# Ambilight-discovery_bachp_V1_2.net
KiCad netlist of a schematic drawn in EAGLE
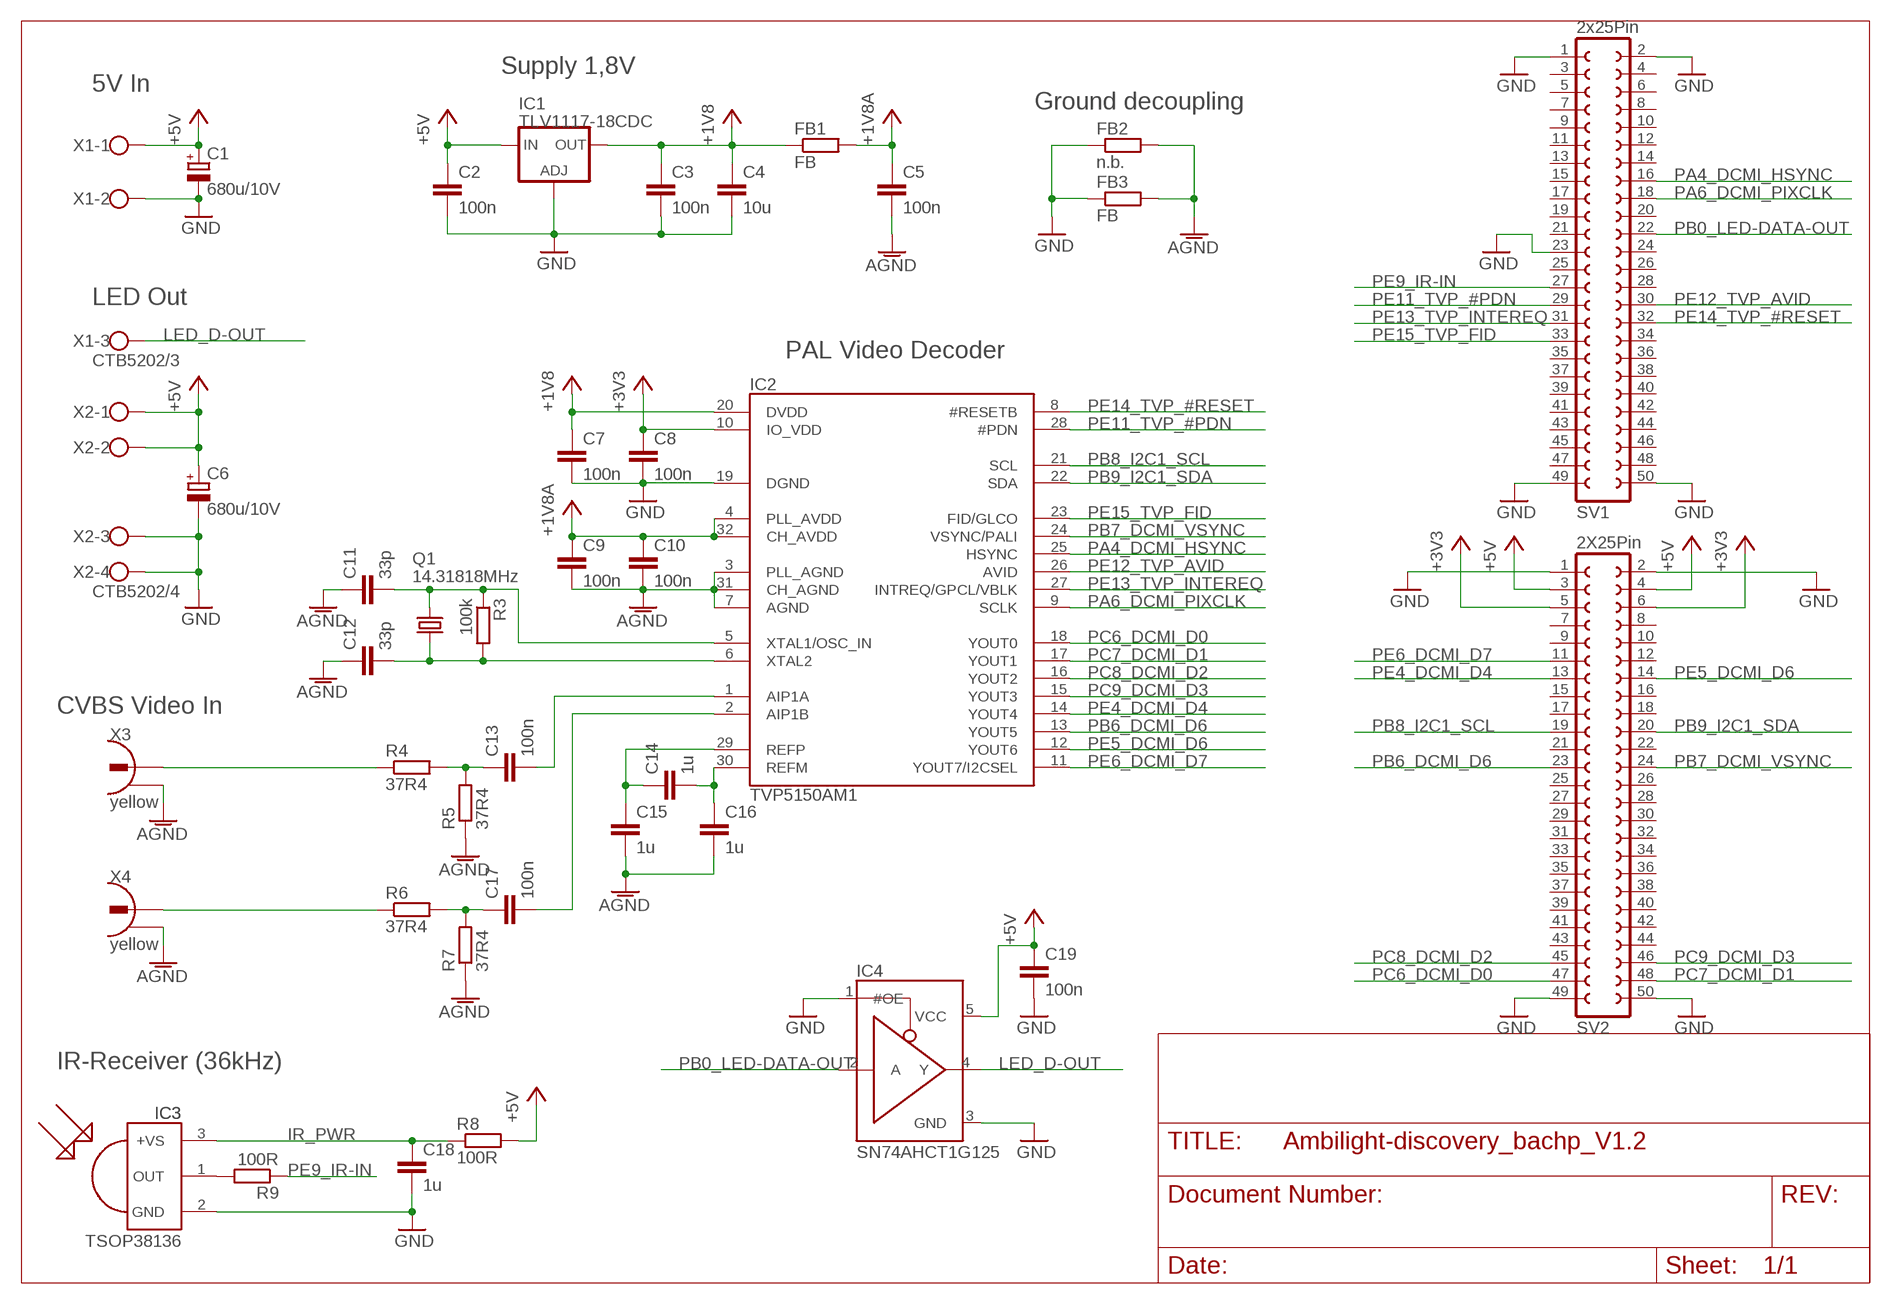
[diagram p0: schematic, sheet 1]

(export (version "E")
  (design (tool "Eeschema 10.0.6"))
  (components
    (comp (ref "C1")
      (value "680u/10V")
      (footprint "eagle-import:153CLV-1012")
      (libsource (lib "eagle-import") (part "CPOL-EU153CLV-1012"))
    )
    (comp (ref "C2")
      (value "100n")
      (footprint "eagle-import:C0805")
      (libsource (lib "eagle-import") (part "C-EUC0805"))
    )
    (comp (ref "C3")
      (value "100n")
      (footprint "eagle-import:C0805")
      (libsource (lib "eagle-import") (part "C-EUC0805"))
    )
    (comp (ref "C4")
      (value "10u")
      (footprint "eagle-import:C1210")
      (libsource (lib "eagle-import") (part "C-EUC1210"))
    )
    (comp (ref "C5")
      (value "100n")
      (footprint "eagle-import:C0805")
      (libsource (lib "eagle-import") (part "C-EUC0805"))
    )
    (comp (ref "C6")
      (value "680u/10V")
      (footprint "eagle-import:153CLV-1012")
      (libsource (lib "eagle-import") (part "CPOL-EU153CLV-1012"))
    )
    (comp (ref "C7")
      (value "100n")
      (footprint "eagle-import:C0805")
      (libsource (lib "eagle-import") (part "C-EUC0805"))
    )
    (comp (ref "C8")
      (value "100n")
      (footprint "eagle-import:C0805")
      (libsource (lib "eagle-import") (part "C-EUC0805"))
    )
    (comp (ref "C9")
      (value "100n")
      (footprint "eagle-import:C0805")
      (libsource (lib "eagle-import") (part "C-EUC0805"))
    )
    (comp (ref "C10")
      (value "100n")
      (footprint "eagle-import:C0805")
      (libsource (lib "eagle-import") (part "C-EUC0805"))
    )
    (comp (ref "C11")
      (value "33p")
      (footprint "eagle-import:C0805")
      (libsource (lib "eagle-import") (part "C-EUC0805"))
    )
    (comp (ref "C12")
      (value "33p")
      (footprint "eagle-import:C0805")
      (libsource (lib "eagle-import") (part "C-EUC0805"))
    )
    (comp (ref "C13")
      (value "100n")
      (footprint "eagle-import:C0805")
      (libsource (lib "eagle-import") (part "C-EUC0805"))
    )
    (comp (ref "C14")
      (value "1u")
      (footprint "eagle-import:C0805")
      (libsource (lib "eagle-import") (part "C-EUC0805"))
    )
    (comp (ref "C15")
      (value "1u")
      (footprint "eagle-import:C0805")
      (libsource (lib "eagle-import") (part "C-EUC0805"))
    )
    (comp (ref "C16")
      (value "1u")
      (footprint "eagle-import:C0805")
      (libsource (lib "eagle-import") (part "C-EUC0805"))
    )
    (comp (ref "C17")
      (value "100n")
      (footprint "eagle-import:C0805")
      (libsource (lib "eagle-import") (part "C-EUC0805"))
    )
    (comp (ref "C18")
      (value "1u")
      (footprint "eagle-import:C0805")
      (libsource (lib "eagle-import") (part "C-EUC0805"))
    )
    (comp (ref "C19")
      (value "100n")
      (footprint "eagle-import:C0805")
      (libsource (lib "eagle-import") (part "C-EUC0805"))
    )
    (comp (ref "FB1")
      (value "FB")
      (footprint "eagle-import:R0805")
      (libsource (lib "eagle-import") (part "R-EU_R0805"))
    )
    (comp (ref "FB2")
      (value "n.b.")
      (footprint "eagle-import:R0805")
      (libsource (lib "eagle-import") (part "R-EU_R0805"))
    )
    (comp (ref "FB3")
      (value "FB")
      (footprint "eagle-import:R0805")
      (libsource (lib "eagle-import") (part "R-EU_R0805"))
    )
    (comp (ref "IC1")
      (value "TLV1117-18CDC")
      (footprint "eagle-import:SOT223")
      (libsource (lib "eagle-import") (part "LD117A?S18TR"))
    )
    (comp (ref "IC2")
      (value "TVP5150AM1")
      (footprint "eagle-import:TQFP32-0.5MM")
      (libsource (lib "eagle-import") (part "TVP5150AM1"))
    )
    (comp (ref "IC3")
      (value "TSOP38136")
      (footprint "eagle-import:TSOP38XXX")
      (libsource (lib "eagle-import") (part "TSOP38136"))
    )
    (comp (ref "IC4")
      (value "SN74AHCT1G125")
      (footprint "eagle-import:SOT23-5L")
      (libsource (lib "eagle-import") (part "SN74AHCT1G125"))
    )
    (comp (ref "Q1")
      (value "14.31818MHz")
      (footprint "eagle-import:HC49UP")
      (libsource (lib "eagle-import") (part "CRYSTALHC49UP"))
    )
    (comp (ref "R3")
      (value "100k")
      (footprint "eagle-import:R0805")
      (libsource (lib "eagle-import") (part "R-EU_R0805"))
    )
    (comp (ref "R4")
      (value "37R4")
      (footprint "eagle-import:R0805")
      (libsource (lib "eagle-import") (part "R-EU_R0805"))
    )
    (comp (ref "R5")
      (value "37R4")
      (footprint "eagle-import:R0805")
      (libsource (lib "eagle-import") (part "R-EU_R0805"))
    )
    (comp (ref "R6")
      (value "37R4")
      (footprint "eagle-import:R0805")
      (libsource (lib "eagle-import") (part "R-EU_R0805"))
    )
    (comp (ref "R7")
      (value "37R4")
      (footprint "eagle-import:R0805")
      (libsource (lib "eagle-import") (part "R-EU_R0805"))
    )
    (comp (ref "R8")
      (value "100R")
      (footprint "eagle-import:R0805")
      (libsource (lib "eagle-import") (part "R-EU_R0805"))
    )
    (comp (ref "R9")
      (value "100R")
      (footprint "eagle-import:R0805")
      (libsource (lib "eagle-import") (part "R-EU_R0805"))
    )
    (comp (ref "SV1")
      (value "2x25Pin")
      (footprint "eagle-import:FE25-2")
      (libsource (lib "eagle-import") (part "FE25-2"))
    )
    (comp (ref "SV2")
      (value "2X25Pin")
      (footprint "eagle-import:FE25-2")
      (libsource (lib "eagle-import") (part "FE25-2"))
    )
    (comp (ref "X1")
      (value "CTB5202/3")
      (footprint "eagle-import:W237-103")
      (fields (field (name "MPN") "237-103"))
      (libsource (lib "eagle-import") (part "W237-103"))
    )
    (comp (ref "X2")
      (value "CTB5202/4")
      (footprint "eagle-import:W237-4")
      (libsource (lib "eagle-import") (part "W237-4"))
    )
    (comp (ref "X3")
      (value "yellow")
      (footprint "eagle-import:CINCH_JALCO")
      (libsource (lib "eagle-import") (part "CINCH_JALCO"))
    )
    (comp (ref "X4")
      (value "yellow")
      (footprint "eagle-import:CINCH_JALCO")
      (libsource (lib "eagle-import") (part "CINCH_JALCO"))
    )
  )
  (nets
    (net (code "1") (name "+1V8") (class "Default")
      (node (ref "C3") (pin "1") (pinfunction "1_1") (pintype "passive"))
      (node (ref "C4") (pin "1") (pinfunction "1_1") (pintype "passive"))
      (node (ref "C7") (pin "1") (pinfunction "1_1") (pintype "passive"))
      (node (ref "FB1") (pin "1") (pinfunction "1_1") (pintype "passive"))
      (node (ref "IC1") (pin "2") (pinfunction "OUT_2") (pintype "passive"))
      (node (ref "IC1") (pin "4") (pinfunction "OUT_4") (pintype "passive"))
      (node (ref "IC2") (pin "20") (pinfunction "DVDD_20") (pintype "power_in"))
    )
    (net (code "2") (name "+1V8A") (class "Default")
      (node (ref "C10") (pin "1") (pinfunction "1_1") (pintype "passive"))
      (node (ref "C5") (pin "1") (pinfunction "1_1") (pintype "passive"))
      (node (ref "C9") (pin "1") (pinfunction "1_1") (pintype "passive"))
      (node (ref "FB1") (pin "2") (pinfunction "2_2") (pintype "passive"))
      (node (ref "IC2") (pin "32") (pinfunction "CH_AVDD_32") (pintype "power_in"))
      (node (ref "IC2") (pin "4") (pinfunction "PLL_AVDD_4") (pintype "power_in"))
    )
    (net (code "3") (name "+3V3") (class "Default")
      (node (ref "C8") (pin "1") (pinfunction "1_1") (pintype "passive"))
      (node (ref "IC2") (pin "10") (pinfunction "IO_VDD_10") (pintype "power_in"))
      (node (ref "SV2") (pin "5") (pinfunction "5_5") (pintype "passive"))
      (node (ref "SV2") (pin "6") (pinfunction "6_6") (pintype "passive"))
    )
    (net (code "4") (name "+5V") (class "Default")
      (node (ref "C1") (pin "+") (pinfunction "+_+") (pintype "passive"))
      (node (ref "C19") (pin "1") (pinfunction "1_1") (pintype "passive"))
      (node (ref "C2") (pin "1") (pinfunction "1_1") (pintype "passive"))
      (node (ref "C6") (pin "+") (pinfunction "+_+") (pintype "passive"))
      (node (ref "IC1") (pin "3") (pinfunction "IN_3") (pintype "input"))
      (node (ref "IC4") (pin "5") (pinfunction "VCC_5") (pintype "power_in"))
      (node (ref "R8") (pin "2") (pinfunction "2_2") (pintype "passive"))
      (node (ref "SV2") (pin "3") (pinfunction "3_3") (pintype "passive"))
      (node (ref "SV2") (pin "4") (pinfunction "4_4") (pintype "passive"))
      (node (ref "X1") (pin "1") (pinfunction "KL_1") (pintype "passive"))
      (node (ref "X2") (pin "1") (pinfunction "KL_1") (pintype "passive"))
      (node (ref "X2") (pin "2") (pinfunction "KL_2") (pintype "passive"))
    )
    (net (code "5") (name "/IR_PWR") (class "Default")
      (node (ref "C18") (pin "1") (pinfunction "1_1") (pintype "passive"))
      (node (ref "IC3") (pin "3") (pinfunction "+VS_3") (pintype "power_in"))
      (node (ref "R8") (pin "1") (pinfunction "1_1") (pintype "passive"))
    )
    (net (code "6") (name "/LED_D-OUT") (class "Default")
      (node (ref "IC4") (pin "4") (pinfunction "Y_4") (pintype "output"))
      (node (ref "X1") (pin "3") (pinfunction "KL_3") (pintype "passive"))
    )
    (net (code "7") (name "/PA4_DCMI_HSYNC") (class "Default")
      (node (ref "IC2") (pin "25") (pinfunction "HSYNC_25") (pintype "output"))
      (node (ref "SV1") (pin "16") (pinfunction "16_16") (pintype "passive"))
    )
    (net (code "8") (name "/PA6_DCMI_PIXCLK") (class "Default")
      (node (ref "IC2") (pin "9") (pinfunction "SCLK_9") (pintype "output"))
      (node (ref "SV1") (pin "18") (pinfunction "18_18") (pintype "passive"))
    )
    (net (code "9") (name "/PB0_LED-DATA-OUT") (class "Default")
      (node (ref "IC4") (pin "2") (pinfunction "A_2") (pintype "input"))
      (node (ref "SV1") (pin "22") (pinfunction "22_22") (pintype "passive"))
    )
    (net (code "10") (name "/PB6_DCMI_D6") (class "Default")
      (node (ref "IC2") (pin "13") (pinfunction "YOUT5_13") (pintype "output"))
      (node (ref "SV2") (pin "23") (pinfunction "23_23") (pintype "passive"))
    )
    (net (code "11") (name "/PB7_DCMI_VSYNC") (class "Default")
      (node (ref "IC2") (pin "24") (pinfunction "VSYNC/PALI_24") (pintype "output"))
      (node (ref "SV2") (pin "24") (pinfunction "24_24") (pintype "passive"))
    )
    (net (code "12") (name "/PB8_I2C1_SCL") (class "Default")
      (node (ref "IC2") (pin "21") (pinfunction "SCL_21") (pintype "bidirectional"))
      (node (ref "SV2") (pin "19") (pinfunction "19_19") (pintype "passive"))
    )
    (net (code "13") (name "/PB9_I2C1_SDA") (class "Default")
      (node (ref "IC2") (pin "22") (pinfunction "SDA_22") (pintype "bidirectional"))
      (node (ref "SV2") (pin "20") (pinfunction "20_20") (pintype "passive"))
    )
    (net (code "14") (name "/PC6_DCMI_D0") (class "Default")
      (node (ref "IC2") (pin "18") (pinfunction "YOUT0_18") (pintype "output"))
      (node (ref "SV2") (pin "47") (pinfunction "47_47") (pintype "passive"))
    )
    (net (code "15") (name "/PC7_DCMI_D1") (class "Default")
      (node (ref "IC2") (pin "17") (pinfunction "YOUT1_17") (pintype "output"))
      (node (ref "SV2") (pin "48") (pinfunction "48_48") (pintype "passive"))
    )
    (net (code "16") (name "/PC8_DCMI_D2") (class "Default")
      (node (ref "IC2") (pin "16") (pinfunction "YOUT2_16") (pintype "output"))
      (node (ref "SV2") (pin "45") (pinfunction "45_45") (pintype "passive"))
    )
    (net (code "17") (name "/PC9_DCMI_D3") (class "Default")
      (node (ref "IC2") (pin "15") (pinfunction "YOUT3_15") (pintype "output"))
      (node (ref "SV2") (pin "46") (pinfunction "46_46") (pintype "passive"))
    )
    (net (code "18") (name "/PE4_DCMI_D4") (class "Default")
      (node (ref "IC2") (pin "14") (pinfunction "YOUT4_14") (pintype "output"))
      (node (ref "SV2") (pin "13") (pinfunction "13_13") (pintype "passive"))
    )
    (net (code "19") (name "/PE5_DCMI_D6") (class "Default")
      (node (ref "IC2") (pin "12") (pinfunction "YOUT6_12") (pintype "output"))
      (node (ref "SV2") (pin "14") (pinfunction "14_14") (pintype "passive"))
    )
    (net (code "20") (name "/PE6_DCMI_D7") (class "Default")
      (node (ref "IC2") (pin "11") (pinfunction "YOUT7/I2CSEL_11") (pintype "bidirectional"))
      (node (ref "SV2") (pin "11") (pinfunction "11_11") (pintype "passive"))
    )
    (net (code "21") (name "/PE9_IR-IN") (class "Default")
      (node (ref "R9") (pin "1") (pinfunction "1_1") (pintype "passive"))
      (node (ref "SV1") (pin "27") (pinfunction "27_27") (pintype "passive"))
    )
    (net (code "22") (name "/PE11_TVP_#PDN") (class "Default")
      (node (ref "IC2") (pin "28") (pinfunction "#PDN_28") (pintype "input"))
      (node (ref "SV1") (pin "29") (pinfunction "29_29") (pintype "passive"))
    )
    (net (code "23") (name "/PE12_TVP_AVID") (class "Default")
      (node (ref "IC2") (pin "26") (pinfunction "AVID_26") (pintype "output"))
      (node (ref "SV1") (pin "30") (pinfunction "30_30") (pintype "passive"))
    )
    (net (code "24") (name "/PE13_TVP_INTEREQ") (class "Default")
      (node (ref "IC2") (pin "27") (pinfunction "INTREQ/GPCL/VBLK_27") (pintype "output"))
      (node (ref "SV1") (pin "31") (pinfunction "31_31") (pintype "passive"))
    )
    (net (code "25") (name "/PE14_TVP_#RESET") (class "Default")
      (node (ref "IC2") (pin "8") (pinfunction "#RESETB_8") (pintype "input"))
      (node (ref "SV1") (pin "32") (pinfunction "32_32") (pintype "passive"))
    )
    (net (code "26") (name "/PE15_TVP_FID") (class "Default")
      (node (ref "IC2") (pin "23") (pinfunction "FID/GLCO_23") (pintype "output"))
      (node (ref "SV1") (pin "33") (pinfunction "33_33") (pintype "passive"))
    )
    (net (code "27") (name "AGND") (class "Default")
      (node (ref "C10") (pin "2") (pinfunction "2_2") (pintype "passive"))
      (node (ref "C11") (pin "1") (pinfunction "1_1") (pintype "passive"))
      (node (ref "C12") (pin "1") (pinfunction "1_1") (pintype "passive"))
      (node (ref "C15") (pin "2") (pinfunction "2_2") (pintype "passive"))
      (node (ref "C16") (pin "2") (pinfunction "2_2") (pintype "passive"))
      (node (ref "C5") (pin "2") (pinfunction "2_2") (pintype "passive"))
      (node (ref "C9") (pin "2") (pinfunction "2_2") (pintype "passive"))
      (node (ref "FB2") (pin "2") (pinfunction "2_2") (pintype "passive"))
      (node (ref "FB3") (pin "2") (pinfunction "2_2") (pintype "passive"))
      (node (ref "IC2") (pin "3") (pinfunction "PLL_AGND_3") (pintype "power_in"))
      (node (ref "IC2") (pin "31") (pinfunction "CH_AGND_31") (pintype "power_in"))
      (node (ref "IC2") (pin "7") (pinfunction "AGND_7") (pintype "power_in"))
      (node (ref "R5") (pin "1") (pinfunction "1_1") (pintype "passive"))
      (node (ref "R7") (pin "1") (pinfunction "1_1") (pintype "passive"))
      (node (ref "X3") (pin "2") (pinfunction "2_2") (pintype "passive"))
      (node (ref "X4") (pin "2") (pinfunction "2_2") (pintype "passive"))
    )
    (net (code "28") (name "GND") (class "Default")
      (node (ref "C1") (pin "-") (pinfunction "-_-") (pintype "passive"))
      (node (ref "C18") (pin "2") (pinfunction "2_2") (pintype "passive"))
      (node (ref "C19") (pin "2") (pinfunction "2_2") (pintype "passive"))
      (node (ref "C2") (pin "2") (pinfunction "2_2") (pintype "passive"))
      (node (ref "C3") (pin "2") (pinfunction "2_2") (pintype "passive"))
      (node (ref "C4") (pin "2") (pinfunction "2_2") (pintype "passive"))
      (node (ref "C6") (pin "-") (pinfunction "-_-") (pintype "passive"))
      (node (ref "C7") (pin "2") (pinfunction "2_2") (pintype "passive"))
      (node (ref "C8") (pin "2") (pinfunction "2_2") (pintype "passive"))
      (node (ref "FB2") (pin "1") (pinfunction "1_1") (pintype "passive"))
      (node (ref "FB3") (pin "1") (pinfunction "1_1") (pintype "passive"))
      (node (ref "IC1") (pin "1") (pinfunction "ADJ_1") (pintype "input"))
      (node (ref "IC2") (pin "19") (pinfunction "DGND_19") (pintype "power_in"))
      (node (ref "IC3") (pin "2") (pinfunction "GND_2") (pintype "power_in"))
      (node (ref "IC4") (pin "1") (pinfunction "#OE_1") (pintype "input"))
      (node (ref "IC4") (pin "3") (pinfunction "GND_3") (pintype "power_in"))
      (node (ref "SV1") (pin "1") (pinfunction "1_1") (pintype "passive"))
      (node (ref "SV1") (pin "2") (pinfunction "2_2") (pintype "passive"))
      (node (ref "SV1") (pin "23") (pinfunction "23_23") (pintype "passive"))
      (node (ref "SV1") (pin "49") (pinfunction "49_49") (pintype "passive"))
      (node (ref "SV1") (pin "50") (pinfunction "50_50") (pintype "passive"))
      (node (ref "SV2") (pin "1") (pinfunction "1_1") (pintype "passive"))
      (node (ref "SV2") (pin "2") (pinfunction "2_2") (pintype "passive"))
      (node (ref "SV2") (pin "49") (pinfunction "49_49") (pintype "passive"))
      (node (ref "SV2") (pin "50") (pinfunction "50_50") (pintype "passive"))
      (node (ref "X1") (pin "2") (pinfunction "KL_2") (pintype "passive"))
      (node (ref "X2") (pin "3") (pinfunction "KL_3") (pintype "passive"))
      (node (ref "X2") (pin "4") (pinfunction "KL_4") (pintype "passive"))
    )
    (net (code "29") (name "Net-(C13-Pad1)") (class "Default")
      (node (ref "C13") (pin "1") (pinfunction "1_1") (pintype "passive"))
      (node (ref "R4") (pin "2") (pinfunction "2_2") (pintype "passive"))
      (node (ref "R5") (pin "2") (pinfunction "2_2") (pintype "passive"))
    )
    (net (code "30") (name "Net-(C17-Pad1)") (class "Default")
      (node (ref "C17") (pin "1") (pinfunction "1_1") (pintype "passive"))
      (node (ref "R6") (pin "2") (pinfunction "2_2") (pintype "passive"))
      (node (ref "R7") (pin "2") (pinfunction "2_2") (pintype "passive"))
    )
    (net (code "31") (name "Net-(IC2-AIP1A)") (class "Default")
      (node (ref "C13") (pin "2") (pinfunction "2_2") (pintype "passive"))
      (node (ref "IC2") (pin "1") (pinfunction "AIP1A_1") (pintype "input"))
    )
    (net (code "32") (name "Net-(IC2-AIP1B)") (class "Default")
      (node (ref "C17") (pin "2") (pinfunction "2_2") (pintype "passive"))
      (node (ref "IC2") (pin "2") (pinfunction "AIP1B_2") (pintype "input"))
    )
    (net (code "33") (name "Net-(IC2-REFM)") (class "Default")
      (node (ref "C14") (pin "2") (pinfunction "2_2") (pintype "passive"))
      (node (ref "C16") (pin "1") (pinfunction "1_1") (pintype "passive"))
      (node (ref "IC2") (pin "30") (pinfunction "REFM_30") (pintype "output"))
    )
    (net (code "34") (name "Net-(IC2-REFP)") (class "Default")
      (node (ref "C14") (pin "1") (pinfunction "1_1") (pintype "passive"))
      (node (ref "C15") (pin "1") (pinfunction "1_1") (pintype "passive"))
      (node (ref "IC2") (pin "29") (pinfunction "REFP_29") (pintype "output"))
    )
    (net (code "35") (name "Net-(IC2-XTAL1{slash}OSC_IN)") (class "Default")
      (node (ref "C11") (pin "2") (pinfunction "2_2") (pintype "passive"))
      (node (ref "IC2") (pin "5") (pinfunction "XTAL1/OSC_IN_5") (pintype "input"))
      (node (ref "Q1") (pin "1") (pinfunction "1_1") (pintype "passive"))
      (node (ref "R3") (pin "1") (pinfunction "1_1") (pintype "passive"))
    )
    (net (code "36") (name "Net-(IC2-XTAL2)") (class "Default")
      (node (ref "C12") (pin "2") (pinfunction "2_2") (pintype "passive"))
      (node (ref "IC2") (pin "6") (pinfunction "XTAL2_6") (pintype "output"))
      (node (ref "Q1") (pin "2") (pinfunction "2_2") (pintype "passive"))
      (node (ref "R3") (pin "2") (pinfunction "2_2") (pintype "passive"))
    )
    (net (code "37") (name "Net-(IC3-OUT)") (class "Default")
      (node (ref "IC3") (pin "1") (pinfunction "OUT_1") (pintype "output"))
      (node (ref "R9") (pin "2") (pinfunction "2_2") (pintype "passive"))
    )
    (net (code "38") (name "Net-(R4-Pad1)") (class "Default")
      (node (ref "R4") (pin "1") (pinfunction "1_1") (pintype "passive"))
      (node (ref "X3") (pin "1") (pinfunction "1_1") (pintype "passive"))
    )
    (net (code "39") (name "Net-(R6-Pad1)") (class "Default")
      (node (ref "R6") (pin "1") (pinfunction "1_1") (pintype "passive"))
      (node (ref "X4") (pin "1") (pinfunction "1_1") (pintype "passive"))
    )
    (net (code "40") (name "unconnected-(SV1-Pad3)") (class "Default")
      (node (ref "SV1") (pin "3") (pinfunction "3_3") (pintype "passive"))
    )
    (net (code "41") (name "unconnected-(SV1-Pad4)") (class "Default")
      (node (ref "SV1") (pin "4") (pinfunction "4_4") (pintype "passive"))
    )
    (net (code "42") (name "unconnected-(SV1-Pad5)") (class "Default")
      (node (ref "SV1") (pin "5") (pinfunction "5_5") (pintype "passive"))
    )
    (net (code "43") (name "unconnected-(SV1-Pad6)") (class "Default")
      (node (ref "SV1") (pin "6") (pinfunction "6_6") (pintype "passive"))
    )
    (net (code "44") (name "unconnected-(SV1-Pad7)") (class "Default")
      (node (ref "SV1") (pin "7") (pinfunction "7_7") (pintype "passive"))
    )
    (net (code "45") (name "unconnected-(SV1-Pad8)") (class "Default")
      (node (ref "SV1") (pin "8") (pinfunction "8_8") (pintype "passive"))
    )
    (net (code "46") (name "unconnected-(SV1-Pad9)") (class "Default")
      (node (ref "SV1") (pin "9") (pinfunction "9_9") (pintype "passive"))
    )
    (net (code "47") (name "unconnected-(SV1-Pad10)") (class "Default")
      (node (ref "SV1") (pin "10") (pinfunction "10_10") (pintype "passive"))
    )
    (net (code "48") (name "unconnected-(SV1-Pad11)") (class "Default")
      (node (ref "SV1") (pin "11") (pinfunction "11_11") (pintype "passive"))
    )
    (net (code "49") (name "unconnected-(SV1-Pad12)") (class "Default")
      (node (ref "SV1") (pin "12") (pinfunction "12_12") (pintype "passive"))
    )
    (net (code "50") (name "unconnected-(SV1-Pad13)") (class "Default")
      (node (ref "SV1") (pin "13") (pinfunction "13_13") (pintype "passive"))
    )
    (net (code "51") (name "unconnected-(SV1-Pad14)") (class "Default")
      (node (ref "SV1") (pin "14") (pinfunction "14_14") (pintype "passive"))
    )
    (net (code "52") (name "unconnected-(SV1-Pad15)") (class "Default")
      (node (ref "SV1") (pin "15") (pinfunction "15_15") (pintype "passive"))
    )
    (net (code "53") (name "unconnected-(SV1-Pad17)") (class "Default")
      (node (ref "SV1") (pin "17") (pinfunction "17_17") (pintype "passive"))
    )
    (net (code "54") (name "unconnected-(SV1-Pad19)") (class "Default")
      (node (ref "SV1") (pin "19") (pinfunction "19_19") (pintype "passive"))
    )
    (net (code "55") (name "unconnected-(SV1-Pad20)") (class "Default")
      (node (ref "SV1") (pin "20") (pinfunction "20_20") (pintype "passive"))
    )
    (net (code "56") (name "unconnected-(SV1-Pad21)") (class "Default")
      (node (ref "SV1") (pin "21") (pinfunction "21_21") (pintype "passive"))
    )
    (net (code "57") (name "unconnected-(SV1-Pad24)") (class "Default")
      (node (ref "SV1") (pin "24") (pinfunction "24_24") (pintype "passive"))
    )
    (net (code "58") (name "unconnected-(SV1-Pad25)") (class "Default")
      (node (ref "SV1") (pin "25") (pinfunction "25_25") (pintype "passive"))
    )
    (net (code "59") (name "unconnected-(SV1-Pad26)") (class "Default")
      (node (ref "SV1") (pin "26") (pinfunction "26_26") (pintype "passive"))
    )
    (net (code "60") (name "unconnected-(SV1-Pad28)") (class "Default")
      (node (ref "SV1") (pin "28") (pinfunction "28_28") (pintype "passive"))
    )
    (net (code "61") (name "unconnected-(SV1-Pad34)") (class "Default")
      (node (ref "SV1") (pin "34") (pinfunction "34_34") (pintype "passive"))
    )
    (net (code "62") (name "unconnected-(SV1-Pad35)") (class "Default")
      (node (ref "SV1") (pin "35") (pinfunction "35_35") (pintype "passive"))
    )
    (net (code "63") (name "unconnected-(SV1-Pad36)") (class "Default")
      (node (ref "SV1") (pin "36") (pinfunction "36_36") (pintype "passive"))
    )
    (net (code "64") (name "unconnected-(SV1-Pad37)") (class "Default")
      (node (ref "SV1") (pin "37") (pinfunction "37_37") (pintype "passive"))
    )
    (net (code "65") (name "unconnected-(SV1-Pad38)") (class "Default")
      (node (ref "SV1") (pin "38") (pinfunction "38_38") (pintype "passive"))
    )
    (net (code "66") (name "unconnected-(SV1-Pad39)") (class "Default")
      (node (ref "SV1") (pin "39") (pinfunction "39_39") (pintype "passive"))
    )
    (net (code "67") (name "unconnected-(SV1-Pad40)") (class "Default")
      (node (ref "SV1") (pin "40") (pinfunction "40_40") (pintype "passive"))
    )
    (net (code "68") (name "unconnected-(SV1-Pad41)") (class "Default")
      (node (ref "SV1") (pin "41") (pinfunction "41_41") (pintype "passive"))
    )
    (net (code "69") (name "unconnected-(SV1-Pad42)") (class "Default")
      (node (ref "SV1") (pin "42") (pinfunction "42_42") (pintype "passive"))
    )
    (net (code "70") (name "unconnected-(SV1-Pad43)") (class "Default")
      (node (ref "SV1") (pin "43") (pinfunction "43_43") (pintype "passive"))
    )
    (net (code "71") (name "unconnected-(SV1-Pad44)") (class "Default")
      (node (ref "SV1") (pin "44") (pinfunction "44_44") (pintype "passive"))
    )
    (net (code "72") (name "unconnected-(SV1-Pad45)") (class "Default")
      (node (ref "SV1") (pin "45") (pinfunction "45_45") (pintype "passive"))
    )
    (net (code "73") (name "unconnected-(SV1-Pad46)") (class "Default")
      (node (ref "SV1") (pin "46") (pinfunction "46_46") (pintype "passive"))
    )
    (net (code "74") (name "unconnected-(SV1-Pad47)") (class "Default")
      (node (ref "SV1") (pin "47") (pinfunction "47_47") (pintype "passive"))
    )
    (net (code "75") (name "unconnected-(SV1-Pad48)") (class "Default")
      (node (ref "SV1") (pin "48") (pinfunction "48_48") (pintype "passive"))
    )
    (net (code "76") (name "unconnected-(SV2-Pad7)") (class "Default")
      (node (ref "SV2") (pin "7") (pinfunction "7_7") (pintype "passive"))
    )
    (net (code "77") (name "unconnected-(SV2-Pad8)") (class "Default")
      (node (ref "SV2") (pin "8") (pinfunction "8_8") (pintype "passive"))
    )
    (net (code "78") (name "unconnected-(SV2-Pad9)") (class "Default")
      (node (ref "SV2") (pin "9") (pinfunction "9_9") (pintype "passive"))
    )
    (net (code "79") (name "unconnected-(SV2-Pad10)") (class "Default")
      (node (ref "SV2") (pin "10") (pinfunction "10_10") (pintype "passive"))
    )
    (net (code "80") (name "unconnected-(SV2-Pad12)") (class "Default")
      (node (ref "SV2") (pin "12") (pinfunction "12_12") (pintype "passive"))
    )
    (net (code "81") (name "unconnected-(SV2-Pad15)") (class "Default")
      (node (ref "SV2") (pin "15") (pinfunction "15_15") (pintype "passive"))
    )
    (net (code "82") (name "unconnected-(SV2-Pad16)") (class "Default")
      (node (ref "SV2") (pin "16") (pinfunction "16_16") (pintype "passive"))
    )
    (net (code "83") (name "unconnected-(SV2-Pad17)") (class "Default")
      (node (ref "SV2") (pin "17") (pinfunction "17_17") (pintype "passive"))
    )
    (net (code "84") (name "unconnected-(SV2-Pad18)") (class "Default")
      (node (ref "SV2") (pin "18") (pinfunction "18_18") (pintype "passive"))
    )
    (net (code "85") (name "unconnected-(SV2-Pad21)") (class "Default")
      (node (ref "SV2") (pin "21") (pinfunction "21_21") (pintype "passive"))
    )
    (net (code "86") (name "unconnected-(SV2-Pad22)") (class "Default")
      (node (ref "SV2") (pin "22") (pinfunction "22_22") (pintype "passive"))
    )
    (net (code "87") (name "unconnected-(SV2-Pad25)") (class "Default")
      (node (ref "SV2") (pin "25") (pinfunction "25_25") (pintype "passive"))
    )
    (net (code "88") (name "unconnected-(SV2-Pad26)") (class "Default")
      (node (ref "SV2") (pin "26") (pinfunction "26_26") (pintype "passive"))
    )
    (net (code "89") (name "unconnected-(SV2-Pad27)") (class "Default")
      (node (ref "SV2") (pin "27") (pinfunction "27_27") (pintype "passive"))
    )
    (net (code "90") (name "unconnected-(SV2-Pad28)") (class "Default")
      (node (ref "SV2") (pin "28") (pinfunction "28_28") (pintype "passive"))
    )
    (net (code "91") (name "unconnected-(SV2-Pad29)") (class "Default")
      (node (ref "SV2") (pin "29") (pinfunction "29_29") (pintype "passive"))
    )
    (net (code "92") (name "unconnected-(SV2-Pad30)") (class "Default")
      (node (ref "SV2") (pin "30") (pinfunction "30_30") (pintype "passive"))
    )
    (net (code "93") (name "unconnected-(SV2-Pad31)") (class "Default")
      (node (ref "SV2") (pin "31") (pinfunction "31_31") (pintype "passive"))
    )
    (net (code "94") (name "unconnected-(SV2-Pad32)") (class "Default")
      (node (ref "SV2") (pin "32") (pinfunction "32_32") (pintype "passive"))
    )
    (net (code "95") (name "unconnected-(SV2-Pad33)") (class "Default")
      (node (ref "SV2") (pin "33") (pinfunction "33_33") (pintype "passive"))
    )
    (net (code "96") (name "unconnected-(SV2-Pad34)") (class "Default")
      (node (ref "SV2") (pin "34") (pinfunction "34_34") (pintype "passive"))
    )
    (net (code "97") (name "unconnected-(SV2-Pad35)") (class "Default")
      (node (ref "SV2") (pin "35") (pinfunction "35_35") (pintype "passive"))
    )
    (net (code "98") (name "unconnected-(SV2-Pad36)") (class "Default")
      (node (ref "SV2") (pin "36") (pinfunction "36_36") (pintype "passive"))
    )
    (net (code "99") (name "unconnected-(SV2-Pad37)") (class "Default")
      (node (ref "SV2") (pin "37") (pinfunction "37_37") (pintype "passive"))
    )
    (net (code "100") (name "unconnected-(SV2-Pad38)") (class "Default")
      (node (ref "SV2") (pin "38") (pinfunction "38_38") (pintype "passive"))
    )
    (net (code "101") (name "unconnected-(SV2-Pad39)") (class "Default")
      (node (ref "SV2") (pin "39") (pinfunction "39_39") (pintype "passive"))
    )
    (net (code "102") (name "unconnected-(SV2-Pad40)") (class "Default")
      (node (ref "SV2") (pin "40") (pinfunction "40_40") (pintype "passive"))
    )
    (net (code "103") (name "unconnected-(SV2-Pad41)") (class "Default")
      (node (ref "SV2") (pin "41") (pinfunction "41_41") (pintype "passive"))
    )
    (net (code "104") (name "unconnected-(SV2-Pad42)") (class "Default")
      (node (ref "SV2") (pin "42") (pinfunction "42_42") (pintype "passive"))
    )
    (net (code "105") (name "unconnected-(SV2-Pad43)") (class "Default")
      (node (ref "SV2") (pin "43") (pinfunction "43_43") (pintype "passive"))
    )
    (net (code "106") (name "unconnected-(SV2-Pad44)") (class "Default")
      (node (ref "SV2") (pin "44") (pinfunction "44_44") (pintype "passive"))
    )
  )
)
